# v2-landshark-handheld-controller.net
KiCad netlist of a schematic drawn in EAGLE
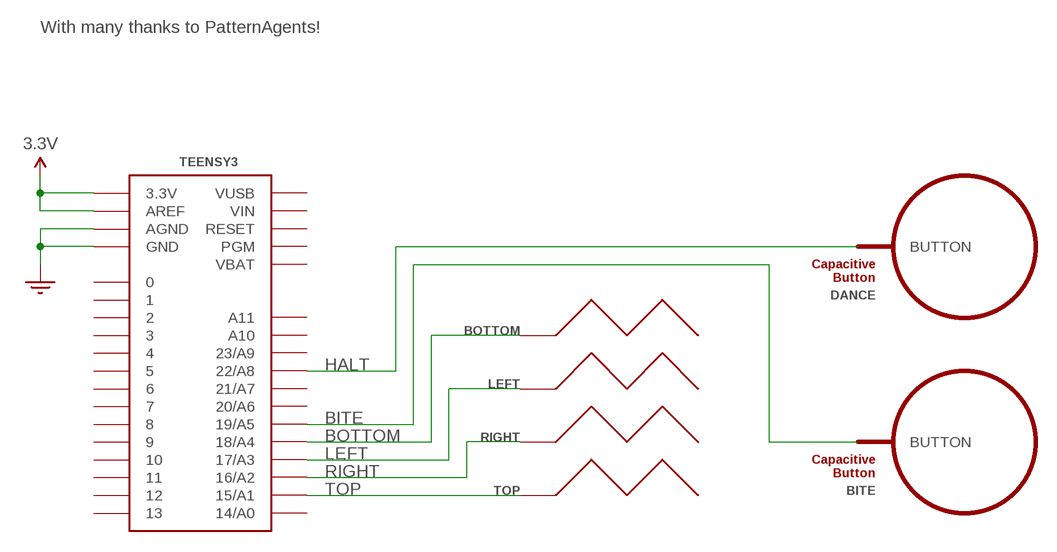
[diagram p0: schematic, sheet 1]

(export (version "E")
  (design (tool "Eeschema 10.0.6"))
  (components
    (comp (ref "BITE")
      (value "BUTTON_PASSIVE_12MM_BITE")
      (footprint "eagle-import:BUTTON_PASSIVE_12MM_BITE")
      (libsource (lib "eagle-import") (part "BUTTON_PASSIVE_12MM_BITE"))
    )
    (comp (ref "BOTTOM")
      (value "SLIDER_PASSIVE_1SEG")
      (footprint "eagle-import:SLIDER_PASSIVE_1SEG_12MM")
      (libsource (lib "eagle-import") (part "SLIDER_PASSIVE_1SEG"))
    )
    (comp (ref "DANCE")
      (value "BUTTON_PASSIVE_12MM_DANCE")
      (footprint "eagle-import:BUTTON_PASSIVE_12MM_DANCE")
      (libsource (lib "eagle-import") (part "BUTTON_PASSIVE_12MM_DANCE"))
    )
    (comp (ref "LEFT")
      (value "SLIDER_PASSIVE_1SEG")
      (footprint "eagle-import:SLIDER_PASSIVE_1SEG_12MM")
      (libsource (lib "eagle-import") (part "SLIDER_PASSIVE_1SEG"))
    )
    (comp (ref "RIGHT")
      (value "SLIDER_PASSIVE_1SEG")
      (footprint "eagle-import:SLIDER_PASSIVE_1SEG_12MM")
      (libsource (lib "eagle-import") (part "SLIDER_PASSIVE_1SEG"))
    )
    (comp (ref "TEENSY3")
      (value "TEENSY_3.0+4")
      (footprint "eagle-import:TEENSY_3.0+4")
      (libsource (lib "eagle-import") (part "TEENSY_3.0+4"))
    )
    (comp (ref "TOP")
      (value "SLIDER_PASSIVE_1SEG")
      (footprint "eagle-import:SLIDER_PASSIVE_1SEG_12MM")
      (libsource (lib "eagle-import") (part "SLIDER_PASSIVE_1SEG"))
    )
  )
  (nets
    (net (code "1") (name "/BITE") (class "Default")
      (node (ref "BITE") (pin "BUTTON") (pinfunction "BUTTON_BUTTON") (pintype "passive"))
      (node (ref "TEENSY3") (pin "19/A5") (pinfunction "19/A5_19/A5") (pintype "bidirectional"))
    )
    (net (code "2") (name "/BOTTOM") (class "Default")
      (node (ref "BOTTOM") (pin "P$1") (pinfunction "SL1_P$1") (pintype "passive"))
      (node (ref "TEENSY3") (pin "18/A4") (pinfunction "18/A4_18/A4") (pintype "bidirectional"))
    )
    (net (code "3") (name "/HALT") (class "Default")
      (node (ref "DANCE") (pin "BUTTON") (pinfunction "BUTTON_BUTTON") (pintype "passive"))
      (node (ref "TEENSY3") (pin "22/A8") (pinfunction "22/A8_22/A8") (pintype "bidirectional"))
    )
    (net (code "4") (name "/LEFT") (class "Default")
      (node (ref "LEFT") (pin "P$1") (pinfunction "SL1_P$1") (pintype "passive"))
      (node (ref "TEENSY3") (pin "17/A3") (pinfunction "17/A3_17/A3") (pintype "bidirectional"))
    )
    (net (code "5") (name "/RIGHT") (class "Default")
      (node (ref "RIGHT") (pin "P$1") (pinfunction "SL1_P$1") (pintype "passive"))
      (node (ref "TEENSY3") (pin "16/A2") (pinfunction "16/A2_16/A2") (pintype "bidirectional"))
    )
    (net (code "6") (name "/TOP") (class "Default")
      (node (ref "TEENSY3") (pin "15/A1") (pinfunction "15/A1_15/A1") (pintype "bidirectional"))
      (node (ref "TOP") (pin "P$1") (pinfunction "SL1_P$1") (pintype "passive"))
    )
    (net (code "7") (name "/VBAT") (class "Default")
      (node (ref "TEENSY3") (pin "VBAT") (pinfunction "VBAT_VBAT") (pintype "power_in"))
    )
    (net (code "8") (name "/VIN") (class "Default")
      (node (ref "TEENSY3") (pin "VIN") (pinfunction "VIN_VIN") (pintype "power_in"))
    )
    (net (code "9") (name "/VUSB") (class "Default")
      (node (ref "TEENSY3") (pin "VUSB") (pinfunction "VUSB_VUSB") (pintype "power_in"))
    )
    (net (code "10") (name "3.3V") (class "Default")
      (node (ref "TEENSY3") (pin "3.3V") (pinfunction "3.3V_3.3V") (pintype "power_in"))
      (node (ref "TEENSY3") (pin "3.3V1") (pinfunction "3.3V_3.3V1") (pintype "power_in"))
      (node (ref "TEENSY3") (pin "AREF") (pinfunction "AREF_AREF") (pintype "power_in"))
    )
    (net (code "11") (name "GND") (class "Default")
      (node (ref "TEENSY3") (pin "AGND") (pinfunction "AGND_AGND") (pintype "power_in"))
      (node (ref "TEENSY3") (pin "GND") (pinfunction "GND_GND") (pintype "power_in"))
      (node (ref "TEENSY3") (pin "GND1") (pinfunction "GND_GND1") (pintype "power_in"))
    )
    (net (code "12") (name "unconnected-(TEENSY3-Pad0)") (class "Default")
      (node (ref "TEENSY3") (pin "0") (pinfunction "0_0") (pintype "bidirectional"))
    )
    (net (code "13") (name "unconnected-(TEENSY3-Pad1)") (class "Default")
      (node (ref "TEENSY3") (pin "1") (pinfunction "1_1") (pintype "bidirectional"))
    )
    (net (code "14") (name "unconnected-(TEENSY3-Pad2)") (class "Default")
      (node (ref "TEENSY3") (pin "2") (pinfunction "2_2") (pintype "bidirectional"))
    )
    (net (code "15") (name "unconnected-(TEENSY3-Pad3)") (class "Default")
      (node (ref "TEENSY3") (pin "3") (pinfunction "3_3") (pintype "bidirectional"))
    )
    (net (code "16") (name "unconnected-(TEENSY3-Pad4)") (class "Default")
      (node (ref "TEENSY3") (pin "4") (pinfunction "4_4") (pintype "bidirectional"))
    )
    (net (code "17") (name "unconnected-(TEENSY3-Pad5)") (class "Default")
      (node (ref "TEENSY3") (pin "5") (pinfunction "5_5") (pintype "bidirectional"))
    )
    (net (code "18") (name "unconnected-(TEENSY3-Pad6)") (class "Default")
      (node (ref "TEENSY3") (pin "6") (pinfunction "6_6") (pintype "bidirectional"))
    )
    (net (code "19") (name "unconnected-(TEENSY3-Pad7)") (class "Default")
      (node (ref "TEENSY3") (pin "7") (pinfunction "7_7") (pintype "bidirectional"))
    )
    (net (code "20") (name "unconnected-(TEENSY3-Pad8)") (class "Default")
      (node (ref "TEENSY3") (pin "8") (pinfunction "8_8") (pintype "bidirectional"))
    )
    (net (code "21") (name "unconnected-(TEENSY3-Pad9)") (class "Default")
      (node (ref "TEENSY3") (pin "9") (pinfunction "9_9") (pintype "bidirectional"))
    )
    (net (code "22") (name "unconnected-(TEENSY3-Pad10)") (class "Default")
      (node (ref "TEENSY3") (pin "10") (pinfunction "10_10") (pintype "bidirectional"))
    )
    (net (code "23") (name "unconnected-(TEENSY3-Pad11)") (class "Default")
      (node (ref "TEENSY3") (pin "11") (pinfunction "11_11") (pintype "bidirectional"))
    )
    (net (code "24") (name "unconnected-(TEENSY3-Pad12)") (class "Default")
      (node (ref "TEENSY3") (pin "12") (pinfunction "12_12") (pintype "bidirectional"))
    )
    (net (code "25") (name "unconnected-(TEENSY3-Pad13)") (class "Default")
      (node (ref "TEENSY3") (pin "13") (pinfunction "13_13") (pintype "bidirectional"))
    )
    (net (code "26") (name "unconnected-(TEENSY3-Pad14{slash}A0)") (class "Default")
      (node (ref "TEENSY3") (pin "14/A0") (pinfunction "14/A0_14/A0") (pintype "bidirectional"))
    )
    (net (code "27") (name "unconnected-(TEENSY3-Pad20{slash}A6)") (class "Default")
      (node (ref "TEENSY3") (pin "20/A6") (pinfunction "20/A6_20/A6") (pintype "bidirectional"))
    )
    (net (code "28") (name "unconnected-(TEENSY3-Pad21{slash}A7)") (class "Default")
      (node (ref "TEENSY3") (pin "21/A7") (pinfunction "21/A7_21/A7") (pintype "bidirectional"))
    )
    (net (code "29") (name "unconnected-(TEENSY3-Pad23{slash}A9)") (class "Default")
      (node (ref "TEENSY3") (pin "23/A9") (pinfunction "23/A9_23/A9") (pintype "bidirectional"))
    )
    (net (code "30") (name "unconnected-(TEENSY3-PadA10)") (class "Default")
      (node (ref "TEENSY3") (pin "A10") (pinfunction "A10_A10") (pintype "bidirectional"))
    )
    (net (code "31") (name "unconnected-(TEENSY3-PadA11)") (class "Default")
      (node (ref "TEENSY3") (pin "A11") (pinfunction "A11_A11") (pintype "bidirectional"))
    )
    (net (code "32") (name "unconnected-(TEENSY3-PadPGM)") (class "Default")
      (node (ref "TEENSY3") (pin "PGM") (pinfunction "PGM_PGM") (pintype "bidirectional"))
    )
    (net (code "33") (name "unconnected-(TEENSY3-PadRESET)") (class "Default")
      (node (ref "TEENSY3") (pin "RESET") (pinfunction "RESET_RESET") (pintype "bidirectional"))
    )
  )
)
